# Sensors.net
KiCad netlist of a schematic drawn in Altium Designer
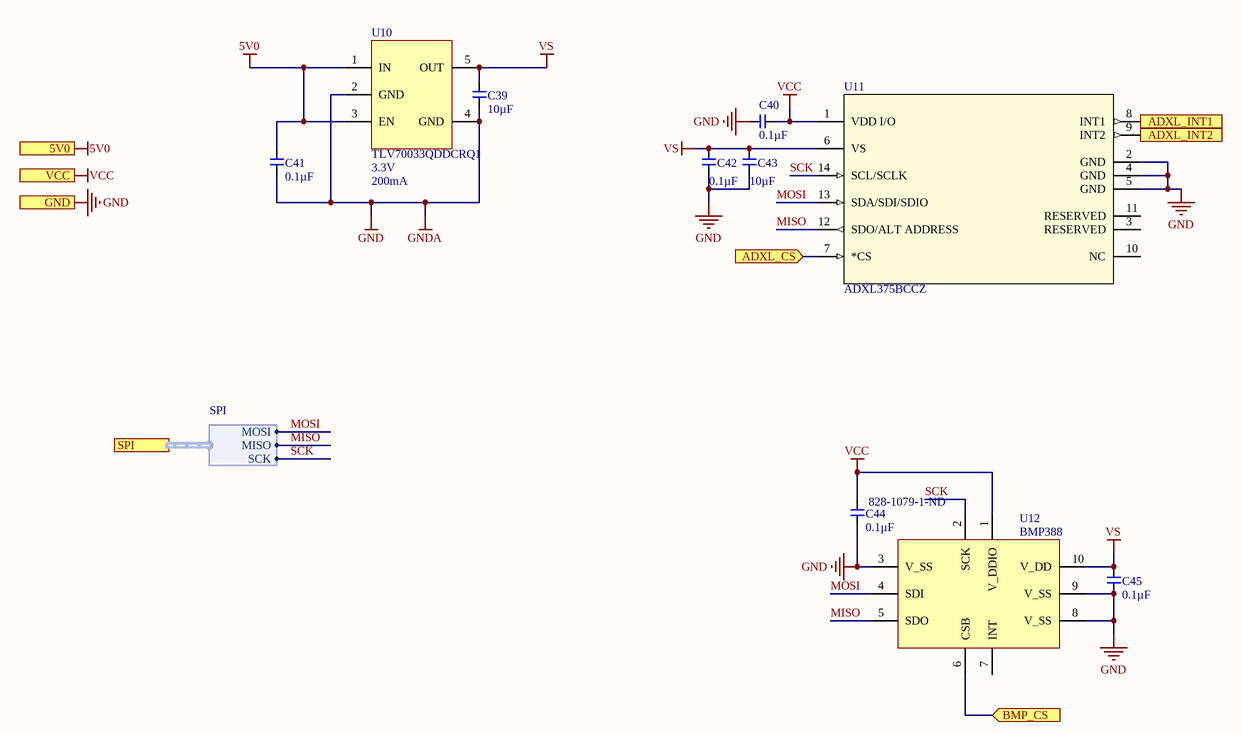
[diagram p0: Sensors.SchDoc]

(export (version "E")
  (design (tool "Eeschema 10.0.6"))
  (components
    (comp (ref "C39")
      (value "__template_cap")
      (footprint "C0603")
      (description "CAP CER 10UF 35V X5R 0603 20%")
      (fields
        (field (name "CAPACITANCE (SHORTHAND)") "10µF")
        (field (name "MANUFACTURER") "Murata Electronics North America")
      )
      (libsource (lib "passives") (part "__template_cap"))
    )
    (comp (ref "C40")
      (value "__template_cap")
      (footprint "C0603")
      (description "CAP CER 0603 0.1µF X7R 50V 10%")
      (fields
        (field (name "CAPACITANCE (SHORTHAND)") "0.1µF")
        (field (name "MANUFACTURER") "Murata Electronics North America")
      )
      (libsource (lib "passives") (part "__template_cap"))
    )
    (comp (ref "C41")
      (value "__template_cap")
      (footprint "C0603")
      (description "CAP CER 0603 0.1µF X7R 50V 10%")
      (fields
        (field (name "CAPACITANCE (SHORTHAND)") "0.1µF")
        (field (name "MANUFACTURER") "Murata Electronics North America")
      )
      (libsource (lib "passives") (part "__template_cap"))
    )
    (comp (ref "C42")
      (value "__template_cap")
      (footprint "C0603")
      (description "CAP CER 0603 0.1µF X7R 50V 10%")
      (fields
        (field (name "CAPACITANCE (SHORTHAND)") "0.1µF")
        (field (name "MANUFACTURER") "Murata Electronics North America")
      )
      (libsource (lib "passives") (part "__template_cap"))
    )
    (comp (ref "C43")
      (value "__template_cap")
      (footprint "C0603")
      (description "CAP CER 10UF 35V X5R 0603 20%")
      (fields
        (field (name "CAPACITANCE (SHORTHAND)") "10µF")
        (field (name "MANUFACTURER") "Murata Electronics North America")
      )
      (libsource (lib "passives") (part "__template_cap"))
    )
    (comp (ref "C44")
      (value "__template_cap")
      (footprint "C0603")
      (description "CAP CER 0603 0.1µF X7R 50V 10%")
      (fields
        (field (name "CAPACITANCE (SHORTHAND)") "0.1µF")
        (field (name "MANUFACTURER") "Murata Electronics North America")
      )
      (libsource (lib "passives") (part "__template_cap"))
    )
    (comp (ref "C45")
      (value "__template_cap")
      (footprint "C0603")
      (description "CAP CER 0603 0.1µF X7R 50V 10%")
      (fields
        (field (name "CAPACITANCE (SHORTHAND)") "0.1µF")
        (field (name "MANUFACTURER") "Murata Electronics North America")
      )
      (libsource (lib "passives") (part "__template_cap"))
    )
    (comp (ref "U10")
      (value "LDO_TLV70033QDDCRQ1")
      (footprint "5SOT23")
      (description "IC REG LDO 3.3V .2A SOT23-5")
      (fields
        (field (name "MANUFACTURER") "Texas Instruments")
        (field (name "MANUFACTURER PART NUMBER") "TLV70033QDDCRQ1")
        (field (name "VOLTAGE - OUTPUT") "3.3V")
        (field (name "CURRENT - OUTPUT") "200mA")
      )
      (libsource (lib "SSI") (part "LDO_TLV70033QDDCRQ1"))
    )
    (comp (ref "U11")
      (value "ADXL375BCCZ")
      (footprint "LGA_CC-14-1")
      (description "200G Accelcerometer")
      (fields
        (field (name "MANUFACTURER") "Analog Devices")
        (field (name "MANUFACTURER PART NUMBER") "ADXL375BCCZ-RL7")
      )
      (libsource (lib "SSI") (part "ADXL375BCCZ"))
    )
    (comp (ref "U12")
      (value "BMP388")
      (footprint "8 pin LGA")
      (description "SENSOR PRESSURE ABS")
      (fields
        (field (name "MANUFACTURER") "Bosch Sensortec")
        (field (name "SUPPLIER PART NUMBER 1") "828-1079-1-ND")
      )
      (libsource (lib "SSI") (part "BMP388"))
    )
  )
  (nets
    (net (code "2") (name "/ADXL_CS") (class "Default")
      (node (ref "U11") (pin "7") (pinfunction "*CS_7") (pintype "input"))
    )
    (net (code "3") (name "/ADXL_INT1") (class "Default")
      (node (ref "U11") (pin "8") (pinfunction "INT1_8") (pintype "output"))
    )
    (net (code "4") (name "/ADXL_INT2") (class "Default")
      (node (ref "U11") (pin "9") (pinfunction "INT2_9") (pintype "output"))
    )
    (net (code "5") (name "/BMP_CS") (class "Default")
      (node (ref "U12") (pin "6") (pinfunction "CSB_6") (pintype "passive"))
    )
    (net (code "6") (name "/MISO") (class "Default")
      (node (ref "U11") (pin "12") (pinfunction "SDO/ALT_ADDRESS_12") (pintype "output"))
      (node (ref "U12") (pin "5") (pinfunction "SDO_5") (pintype "passive"))
    )
    (net (code "7") (name "/MOSI") (class "Default")
      (node (ref "U11") (pin "13") (pinfunction "SDA/SDI/SDIO_13") (pintype "input"))
      (node (ref "U12") (pin "4") (pinfunction "SDI_4") (pintype "passive"))
    )
    (net (code "8") (name "/SCK") (class "Default")
      (node (ref "U11") (pin "14") (pinfunction "SCL/SCLK_14") (pintype "input"))
      (node (ref "U12") (pin "2") (pinfunction "SCK_2") (pintype "passive"))
    )
    (net (code "10") (name "5V0") (class "Default")
      (node (ref "C41") (pin "1") (pintype "passive"))
      (node (ref "U10") (pin "1") (pinfunction "IN_1") (pintype "passive"))
      (node (ref "U10") (pin "3") (pinfunction "EN_3") (pintype "passive"))
    )
    (net (code "11") (name "GND") (class "Default")
      (node (ref "C39") (pin "2") (pintype "passive"))
      (node (ref "C40") (pin "2") (pintype "passive"))
      (node (ref "C41") (pin "2") (pintype "passive"))
      (node (ref "C42") (pin "1") (pintype "passive"))
      (node (ref "C43") (pin "2") (pintype "passive"))
      (node (ref "C44") (pin "2") (pintype "passive"))
      (node (ref "C45") (pin "2") (pintype "passive"))
      (node (ref "U10") (pin "2") (pinfunction "GND_2") (pintype "passive"))
      (node (ref "U10") (pin "4") (pinfunction "GND_4") (pintype "passive"))
      (node (ref "U11") (pin "2") (pinfunction "GND_2") (pintype "power_in"))
      (node (ref "U11") (pin "4") (pinfunction "GND_4") (pintype "power_in"))
      (node (ref "U11") (pin "5") (pinfunction "GND_5") (pintype "power_in"))
      (node (ref "U12") (pin "3") (pinfunction "V_SS_3") (pintype "passive"))
      (node (ref "U12") (pin "8") (pinfunction "V_SS_8") (pintype "passive"))
      (node (ref "U12") (pin "9") (pinfunction "V_SS_9") (pintype "passive"))
    )
    (net (code "12") (name "VCC") (class "Default")
      (node (ref "C40") (pin "1") (pintype "passive"))
      (node (ref "C44") (pin "1") (pintype "passive"))
      (node (ref "U11") (pin "1") (pinfunction "VDD_I/O_1") (pintype "power_in"))
      (node (ref "U12") (pin "1") (pinfunction "V_DDIO_1") (pintype "passive"))
    )
    (net (code "13") (name "VS") (class "Default")
      (node (ref "C39") (pin "1") (pintype "passive"))
      (node (ref "C42") (pin "2") (pintype "passive"))
      (node (ref "C43") (pin "1") (pintype "passive"))
      (node (ref "C45") (pin "1") (pintype "passive"))
      (node (ref "U10") (pin "5") (pinfunction "OUT_5") (pintype "passive"))
      (node (ref "U11") (pin "6") (pinfunction "VS_6") (pintype "power_in"))
      (node (ref "U12") (pin "10") (pinfunction "V_DD_10") (pintype "passive"))
    )
    (net (code "14") (name "unconnected-(U11-NC-Pad10)") (class "Default")
      (node (ref "U11") (pin "10") (pinfunction "NC_10") (pintype "passive"))
    )
    (net (code "15") (name "unconnected-(U11-RESERVED-Pad3)") (class "Default")
      (node (ref "U11") (pin "3") (pinfunction "RESERVED_3") (pintype "passive"))
    )
    (net (code "16") (name "unconnected-(U11-RESERVED-Pad11)") (class "Default")
      (node (ref "U11") (pin "11") (pinfunction "RESERVED_11") (pintype "passive"))
    )
    (net (code "17") (name "unconnected-(U12-INT-Pad7)") (class "Default")
      (node (ref "U12") (pin "7") (pinfunction "INT_7") (pintype "passive"))
    )
  )
)
